# LevelShift.net
KiCad netlist of a schematic drawn in Altium Designer
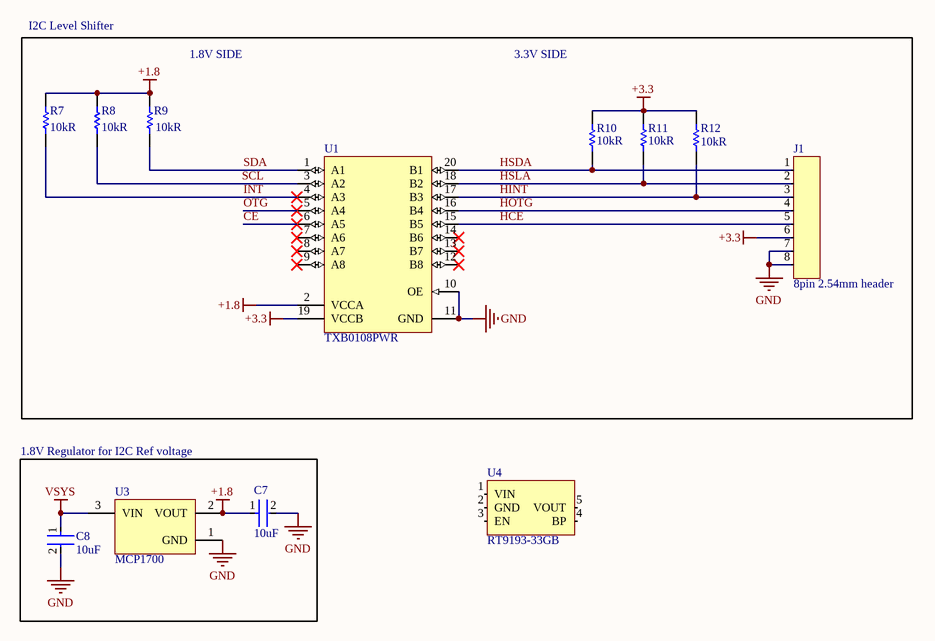
[diagram p0: LevelShift.SchDoc]

(export (version "E")
  (design (tool "Eeschema 10.0.6"))
  (components
    (comp (ref "C7")
      (value "10uF")
      (footprint "FP-C0805C-DG-MFG")
      (description "SMD Comm X5R, Ceramic, 10 uF, 10%, 10 V, X5R, SMD, MLCC, Temperature Stable, Class II, 0805")
      (fields (field (name "TOLERANCE") "10%"))
      (libsource (lib "Altium Content Vault") (part "11868f565c42a9108669ba33697ecf6"))
    )
    (comp (ref "C8")
      (value "10uF")
      (footprint "FP-C0805C-DG-MFG")
      (description "SMD Comm X5R, Ceramic, 10 uF, 10%, 10 V, X5R, SMD, MLCC, Temperature Stable, Class II, 0805")
      (fields (field (name "TOLERANCE") "10%"))
      (libsource (lib "Altium Content Vault") (part "11868f565c42a9108669ba33697ecf6"))
    )
    (comp (ref "J1")
      (value "8pin 2.54mm header")
      (footprint "8pin 2.54mm header")
      (libsource (lib "BQ25895") (part "8pin 2.54mm header"))
    )
    (comp (ref "R7")
      (value "10kR")
      (footprint "RESC2013X60X35NL10T20")
      (description "Chip Resistor, 10 KOhm, +/- 1%, 0.125 W, -55 to 155 degC, 0805 (2012 Metric), RoHS, Tape and Reel")
      (fields (field (name "MANUFACTURER") "Yageo") (field (name "Comment") "RC0805FR-0710KL"))
      (libsource (lib "Altium Content Vault") (part "RES-2"))
    )
    (comp (ref "R8")
      (value "10kR")
      (footprint "RESC2013X60X35NL10T20")
      (description "Chip Resistor, 10 KOhm, +/- 1%, 0.125 W, -55 to 155 degC, 0805 (2012 Metric), RoHS, Tape and Reel")
      (fields (field (name "MANUFACTURER") "Yageo") (field (name "Comment") "RC0805FR-0710KL"))
      (libsource (lib "Altium Content Vault") (part "RES-2"))
    )
    (comp (ref "R9")
      (value "10kR")
      (footprint "RESC2013X60X35NL10T20")
      (description "Chip Resistor, 10 KOhm, +/- 1%, 0.125 W, -55 to 155 degC, 0805 (2012 Metric), RoHS, Tape and Reel")
      (fields (field (name "MANUFACTURER") "Yageo") (field (name "Comment") "RC0805FR-0710KL"))
      (libsource (lib "Altium Content Vault") (part "RES-2"))
    )
    (comp (ref "R10")
      (value "10kR")
      (footprint "RESC2013X60X35NL10T20")
      (description "Chip Resistor, 10 KOhm, +/- 1%, 0.125 W, -55 to 155 degC, 0805 (2012 Metric), RoHS, Tape and Reel")
      (fields (field (name "MANUFACTURER") "Yageo") (field (name "Comment") "RC0805FR-0710KL"))
      (libsource (lib "Altium Content Vault") (part "RES-2"))
    )
    (comp (ref "R11")
      (value "10kR")
      (footprint "RESC2013X60X35NL10T20")
      (description "Chip Resistor, 10 KOhm, +/- 1%, 0.125 W, -55 to 155 degC, 0805 (2012 Metric), RoHS, Tape and Reel")
      (fields (field (name "MANUFACTURER") "Yageo") (field (name "Comment") "RC0805FR-0710KL"))
      (libsource (lib "Altium Content Vault") (part "RES-2"))
    )
    (comp (ref "R12")
      (value "10kR")
      (footprint "RESC2013X60X35NL10T20")
      (description "Chip Resistor, 10 KOhm, +/- 1%, 0.125 W, -55 to 155 degC, 0805 (2012 Metric), RoHS, Tape and Reel")
      (fields (field (name "MANUFACTURER") "Yageo") (field (name "Comment") "RC0805FR-0710KL"))
      (libsource (lib "Altium Content Vault") (part "RES-2"))
    )
    (comp (ref "U1")
      (value "TXB0108PWR")
      (footprint "PW0020A_L")
      (fields (field (name "MANUFACTURER") "Texas Instruments"))
      (libsource (lib "Altium Content Vault") (part "TI-TXB0108-PW-20"))
    )
    (comp (ref "U3")
      (value "MCP1700")
      (footprint "BQ25895:MCP1700-18")
      (description "Fixed Positive LDO Regulator, 1.8V, 0.35V Dropout, CMOS, PDSO3")
      (fields
        (field (name "MANUFACTURER") "Microchip")
        (field (name "MANUFACTURER PART NUMBER") "MCP1700T-1802E/TT")
      )
      (libsource (lib "BQ25895") (part "MCP1700"))
    )
    (comp (ref "U4")
      (value "RT9193-33GB")
      (footprint "SOT-23-5")
      (libsource (lib "BQ25895") (part "RT9193-33GB"))
    )
  )
  (nets
    (net (code "1") (name "+1.8") (class "Default")
      (node (ref "C7") (pin "1") (pinfunction "1_1") (pintype "passive"))
      (node (ref "R7") (pin "1") (pinfunction "1_1") (pintype "passive"))
      (node (ref "R8") (pin "1") (pinfunction "1_1") (pintype "passive"))
      (node (ref "R9") (pin "1") (pinfunction "1_1") (pintype "passive"))
      (node (ref "U1") (pin "2") (pinfunction "VCCA_2") (pintype "power_in"))
      (node (ref "U3") (pin "2") (pinfunction "VOUT_2") (pintype "power_in"))
    )
    (net (code "2") (name "+3.3") (class "Default")
      (node (ref "J1") (pin "6") (pintype "input"))
      (node (ref "R10") (pin "1") (pinfunction "1_1") (pintype "passive"))
      (node (ref "R11") (pin "1") (pinfunction "1_1") (pintype "passive"))
      (node (ref "R12") (pin "1") (pinfunction "1_1") (pintype "passive"))
      (node (ref "U1") (pin "19") (pinfunction "VCCB_19") (pintype "power_in"))
    )
    (net (code "3") (name "/CE") (class "Default")
      (node (ref "U1") (pin "6") (pinfunction "A5_6") (pintype "bidirectional+no_connect"))
    )
    (net (code "4") (name "/HCE") (class "Default")
      (node (ref "J1") (pin "5") (pintype "input"))
      (node (ref "U1") (pin "15") (pinfunction "B5_15") (pintype "bidirectional"))
    )
    (net (code "5") (name "/HINT") (class "Default")
      (node (ref "J1") (pin "3") (pintype "input"))
      (node (ref "R12") (pin "2") (pinfunction "2_2") (pintype "passive"))
      (node (ref "U1") (pin "17") (pinfunction "B3_17") (pintype "bidirectional"))
    )
    (net (code "6") (name "/HOTG") (class "Default")
      (node (ref "J1") (pin "4") (pintype "input"))
      (node (ref "U1") (pin "16") (pinfunction "B4_16") (pintype "bidirectional"))
    )
    (net (code "7") (name "/HSDA") (class "Default")
      (node (ref "J1") (pin "1") (pintype "input"))
      (node (ref "R10") (pin "2") (pinfunction "2_2") (pintype "passive"))
      (node (ref "U1") (pin "20") (pinfunction "B1_20") (pintype "bidirectional"))
    )
    (net (code "8") (name "/HSLA") (class "Default")
      (node (ref "J1") (pin "2") (pintype "input"))
      (node (ref "R11") (pin "2") (pinfunction "2_2") (pintype "passive"))
      (node (ref "U1") (pin "18") (pinfunction "B2_18") (pintype "bidirectional"))
    )
    (net (code "9") (name "/INT") (class "Default")
      (node (ref "R7") (pin "2") (pinfunction "2_2") (pintype "passive"))
      (node (ref "U1") (pin "4") (pinfunction "A3_4") (pintype "bidirectional"))
    )
    (net (code "10") (name "/OTG") (class "Default")
      (node (ref "U1") (pin "5") (pinfunction "A4_5") (pintype "bidirectional+no_connect"))
    )
    (net (code "11") (name "/SCL") (class "Default")
      (node (ref "R8") (pin "2") (pinfunction "2_2") (pintype "passive"))
      (node (ref "U1") (pin "3") (pinfunction "A2_3") (pintype "bidirectional"))
    )
    (net (code "12") (name "/SDA") (class "Default")
      (node (ref "R9") (pin "2") (pinfunction "2_2") (pintype "passive"))
      (node (ref "U1") (pin "1") (pinfunction "A1_1") (pintype "bidirectional"))
    )
    (net (code "13") (name "GND") (class "Default")
      (node (ref "C7") (pin "2") (pinfunction "2_2") (pintype "passive"))
      (node (ref "C8") (pin "2") (pinfunction "2_2") (pintype "passive"))
      (node (ref "J1") (pin "7") (pintype "input"))
      (node (ref "J1") (pin "8") (pintype "input"))
      (node (ref "U1") (pin "10") (pinfunction "OE_10") (pintype "input"))
      (node (ref "U1") (pin "11") (pinfunction "GND_11") (pintype "power_in"))
      (node (ref "U3") (pin "1") (pinfunction "GND_1") (pintype "power_in"))
    )
    (net (code "14") (name "VSYS") (class "Default")
      (node (ref "C8") (pin "1") (pinfunction "1_1") (pintype "passive"))
      (node (ref "U3") (pin "3") (pinfunction "VIN_3") (pintype "power_in"))
    )
    (net (code "15") (name "unconnected-(U1-A6-Pad7)") (class "Default")
      (node (ref "U1") (pin "7") (pinfunction "A6_7") (pintype "bidirectional+no_connect"))
    )
    (net (code "16") (name "unconnected-(U1-A7-Pad8)") (class "Default")
      (node (ref "U1") (pin "8") (pinfunction "A7_8") (pintype "bidirectional+no_connect"))
    )
    (net (code "17") (name "unconnected-(U1-A8-Pad9)") (class "Default")
      (node (ref "U1") (pin "9") (pinfunction "A8_9") (pintype "bidirectional+no_connect"))
    )
    (net (code "18") (name "unconnected-(U1-B6-Pad14)") (class "Default")
      (node (ref "U1") (pin "14") (pinfunction "B6_14") (pintype "bidirectional+no_connect"))
    )
    (net (code "19") (name "unconnected-(U1-B7-Pad13)") (class "Default")
      (node (ref "U1") (pin "13") (pinfunction "B7_13") (pintype "bidirectional+no_connect"))
    )
    (net (code "20") (name "unconnected-(U1-B8-Pad12)") (class "Default")
      (node (ref "U1") (pin "12") (pinfunction "B8_12") (pintype "bidirectional+no_connect"))
    )
    (net (code "21") (name "unconnected-(U4-BP-Pad4)") (class "Default")
      (node (ref "U4") (pin "4") (pinfunction "BP_4") (pintype "input"))
    )
    (net (code "22") (name "unconnected-(U4-EN-Pad3)") (class "Default")
      (node (ref "U4") (pin "3") (pinfunction "EN_3") (pintype "input"))
    )
    (net (code "23") (name "unconnected-(U4-GND-Pad2)") (class "Default")
      (node (ref "U4") (pin "2") (pinfunction "GND_2") (pintype "input"))
    )
    (net (code "24") (name "unconnected-(U4-VIN-Pad1)") (class "Default")
      (node (ref "U4") (pin "1") (pinfunction "VIN_1") (pintype "input"))
    )
    (net (code "25") (name "unconnected-(U4-VOUT-Pad5)") (class "Default")
      (node (ref "U4") (pin "5") (pinfunction "VOUT_5") (pintype "input"))
    )
  )
)
